# 180V_power.net
KiCad netlist of a schematic drawn in EAGLE
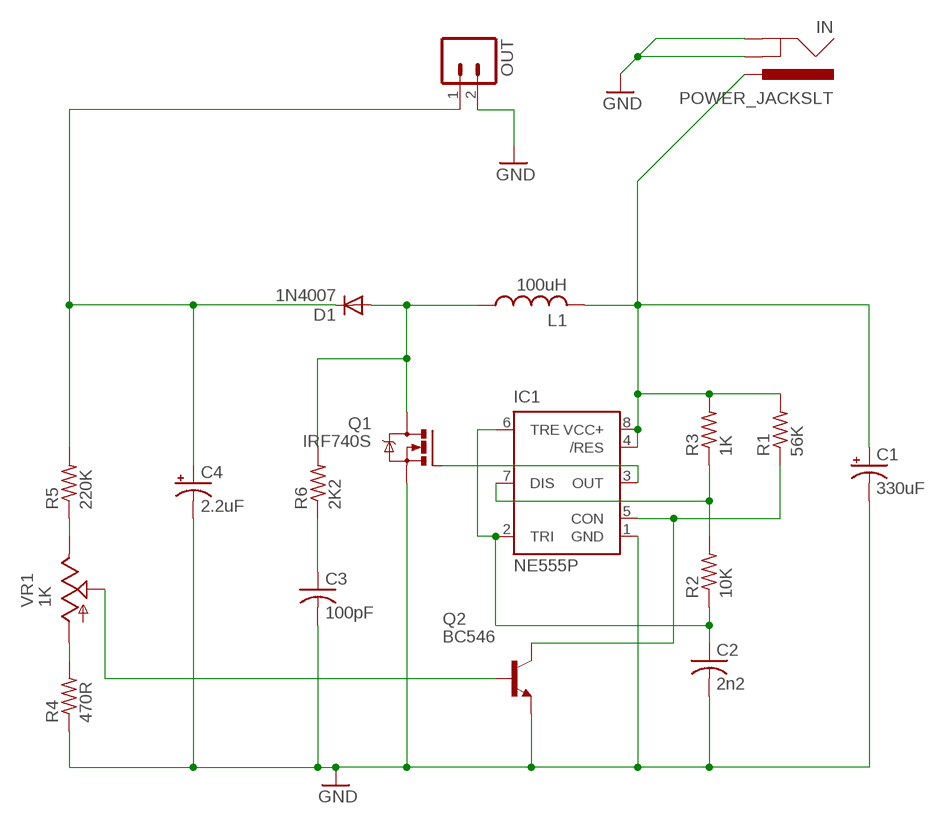
[diagram p0: schematic, sheet 1]

(export (version "E")
  (design (tool "Eeschema 10.0.6"))
  (components
    (comp (ref "C1")
      (value "330uF")
      (footprint "eagle-import:E5-10,5")
      (libsource (lib "eagle-import") (part "CAPACITOR_POLE5-10.5"))
    )
    (comp (ref "C2")
      (value "2n2")
      (footprint "eagle-import:C1206K")
      (libsource (lib "eagle-import") (part "CAPACITORC1206K"))
    )
    (comp (ref "C3")
      (value "100pF")
      (footprint "eagle-import:C1206K")
      (libsource (lib "eagle-import") (part "CAPACITORC1206K"))
    )
    (comp (ref "C4")
      (value "2.2uF")
      (footprint "eagle-import:E3,5-8")
      (libsource (lib "eagle-import") (part "CAPACITOR_POLE3.5-8"))
    )
    (comp (ref "D1")
      (value "1N4007")
      (footprint "eagle-import:SMA-DIODE")
      (libsource (lib "eagle-import") (part "DIODESMA"))
    )
    (comp (ref "IC1")
      (value "NE555P")
      (footprint "eagle-import:DIL08")
      (fields (field (name "MF") "Arrow Electronics") (field (name "MPN") "NE555N"))
      (libsource (lib "eagle-import") (part "NE555P"))
    )
    (comp (ref "IN")
      (value "POWER_JACKSLT")
      (footprint "eagle-import:POWER_JACK_SLOT")
      (libsource (lib "eagle-import") (part "POWER_JACKSLT"))
    )
    (comp (ref "L1")
      (value "100uH")
      (footprint "eagle-import:TFI0307")
      (libsource (lib "eagle-import") (part "INDUCTORTFI0307"))
    )
    (comp (ref "OUT")
      (value "M023.5MM")
      (footprint "eagle-import:SCREWTERMINAL-3.5MM-2")
      (libsource (lib "eagle-import") (part "M023.5MM"))
    )
    (comp (ref "Q1")
      (value "IRF740S")
      (footprint "eagle-import:TO263")
      (libsource (lib "eagle-import") (part "IRF740S"))
    )
    (comp (ref "Q2")
      (value "BC546")
      (footprint "eagle-import:TO92-EBC")
      (libsource (lib "eagle-import") (part "BC546A"))
    )
    (comp (ref "R1")
      (value "56K")
      (footprint "eagle-import:R1206")
      (libsource (lib "eagle-import") (part "RESISTORR1206"))
    )
    (comp (ref "R2")
      (value "10K")
      (footprint "eagle-import:R1206")
      (libsource (lib "eagle-import") (part "RESISTORR1206"))
    )
    (comp (ref "R3")
      (value "1K")
      (footprint "eagle-import:R1206")
      (libsource (lib "eagle-import") (part "RESISTORR1206"))
    )
    (comp (ref "R4")
      (value "470R")
      (footprint "eagle-import:0207_10")
      (libsource (lib "eagle-import") (part "RESISTOR0207/10"))
    )
    (comp (ref "R5")
      (value "220K")
      (footprint "eagle-import:0207_10")
      (libsource (lib "eagle-import") (part "RESISTOR0207/10"))
    )
    (comp (ref "R6")
      (value "2K2")
      (footprint "eagle-import:R1206")
      (libsource (lib "eagle-import") (part "RESISTORR1206"))
    )
    (comp (ref "VR1")
      (value "1K")
      (footprint "eagle-import:CA6V")
      (libsource (lib "eagle-import") (part "TRIM_POTCA6V"))
    )
  )
  (nets
    (net (code "1") (name "GND") (class "Default")
      (node (ref "C1") (pin "-") (pinfunction "-_-") (pintype "passive"))
      (node (ref "C2") (pin "2") (pinfunction "2_2") (pintype "passive"))
      (node (ref "C3") (pin "2") (pinfunction "2_2") (pintype "passive"))
      (node (ref "C4") (pin "-") (pinfunction "-_-") (pintype "passive"))
      (node (ref "IC1") (pin "1") (pinfunction "GND_1") (pintype "power_in"))
      (node (ref "IN") (pin "GND@1") (pinfunction "GNDBREAK_GND@1") (pintype "bidirectional"))
      (node (ref "IN") (pin "GND@2") (pinfunction "GND_GND@2") (pintype "bidirectional"))
      (node (ref "OUT") (pin "2") (pinfunction "2_2") (pintype "passive"))
      (node (ref "Q1") (pin "2") (pinfunction "S_2") (pintype "passive"))
      (node (ref "Q2") (pin "E") (pinfunction "E_E") (pintype "passive"))
      (node (ref "R4") (pin "1") (pinfunction "1_1") (pintype "passive"))
    )
    (net (code "2") (name "Net-(C3-Pad1)") (class "Default")
      (node (ref "C3") (pin "1") (pinfunction "1_1") (pintype "passive"))
      (node (ref "R6") (pin "1") (pinfunction "1_1") (pintype "passive"))
    )
    (net (code "3") (name "Net-(C4-Pad+)") (class "Default")
      (node (ref "C4") (pin "+") (pinfunction "+_+") (pintype "passive"))
      (node (ref "D1") (pin "C") (pinfunction "C_C") (pintype "passive"))
      (node (ref "OUT") (pin "1") (pinfunction "1_1") (pintype "passive"))
      (node (ref "R5") (pin "2") (pinfunction "2_2") (pintype "passive"))
    )
    (net (code "4") (name "Net-(IC1-CON)") (class "Default")
      (node (ref "IC1") (pin "5") (pinfunction "CON_5") (pintype "input"))
      (node (ref "Q2") (pin "C") (pinfunction "C_C") (pintype "passive"))
      (node (ref "R1") (pin "1") (pinfunction "1_1") (pintype "passive"))
    )
    (net (code "5") (name "Net-(IC1-DIS)") (class "Default")
      (node (ref "IC1") (pin "7") (pinfunction "DIS_7") (pintype "input"))
      (node (ref "R2") (pin "2") (pinfunction "2_2") (pintype "passive"))
      (node (ref "R3") (pin "1") (pinfunction "1_1") (pintype "passive"))
    )
    (net (code "6") (name "Net-(IC1-OUT)") (class "Default")
      (node (ref "IC1") (pin "3") (pinfunction "OUT_3") (pintype "output"))
      (node (ref "Q1") (pin "1") (pinfunction "G_1") (pintype "passive"))
    )
    (net (code "7") (name "Net-(IC1-TRE)") (class "Default")
      (node (ref "C2") (pin "1") (pinfunction "1_1") (pintype "passive"))
      (node (ref "IC1") (pin "2") (pinfunction "TRI_2") (pintype "input"))
      (node (ref "IC1") (pin "6") (pinfunction "TRE_6") (pintype "input"))
      (node (ref "R2") (pin "1") (pinfunction "1_1") (pintype "passive"))
    )
    (net (code "8") (name "Net-(IC1-VCC+)") (class "Default")
      (node (ref "C1") (pin "+") (pinfunction "+_+") (pintype "passive"))
      (node (ref "IC1") (pin "4") (pinfunction "/RES_4") (pintype "input"))
      (node (ref "IC1") (pin "8") (pinfunction "VCC+_8") (pintype "power_in"))
      (node (ref "IN") (pin "PWR") (pinfunction "PWR_PWR") (pintype "bidirectional"))
      (node (ref "L1") (pin "2") (pinfunction "2_2") (pintype "passive"))
      (node (ref "R1") (pin "2") (pinfunction "2_2") (pintype "passive"))
      (node (ref "R3") (pin "2") (pinfunction "2_2") (pintype "passive"))
    )
    (net (code "9") (name "Net-(Q1-D)") (class "Default")
      (node (ref "D1") (pin "A") (pinfunction "A_A") (pintype "passive"))
      (node (ref "L1") (pin "1") (pinfunction "1_1") (pintype "passive"))
      (node (ref "Q1") (pin "3") (pinfunction "D_3") (pintype "passive"))
      (node (ref "R6") (pin "2") (pinfunction "2_2") (pintype "passive"))
    )
    (net (code "10") (name "Net-(Q2-PadB)") (class "Default")
      (node (ref "Q2") (pin "B") (pinfunction "B_B") (pintype "passive"))
      (node (ref "VR1") (pin "S") (pinfunction "S_S") (pintype "passive"))
    )
    (net (code "11") (name "Net-(R4-Pad2)") (class "Default")
      (node (ref "R4") (pin "2") (pinfunction "2_2") (pintype "passive"))
      (node (ref "VR1") (pin "A") (pinfunction "A_A") (pintype "passive"))
    )
    (net (code "12") (name "Net-(R5-Pad1)") (class "Default")
      (node (ref "R5") (pin "1") (pinfunction "1_1") (pintype "passive"))
      (node (ref "VR1") (pin "E") (pinfunction "E_E") (pintype "passive"))
    )
  )
)
